# PCB_PSU_DCDC_001_A1.net
KiCad netlist of a schematic drawn in Altium Designer
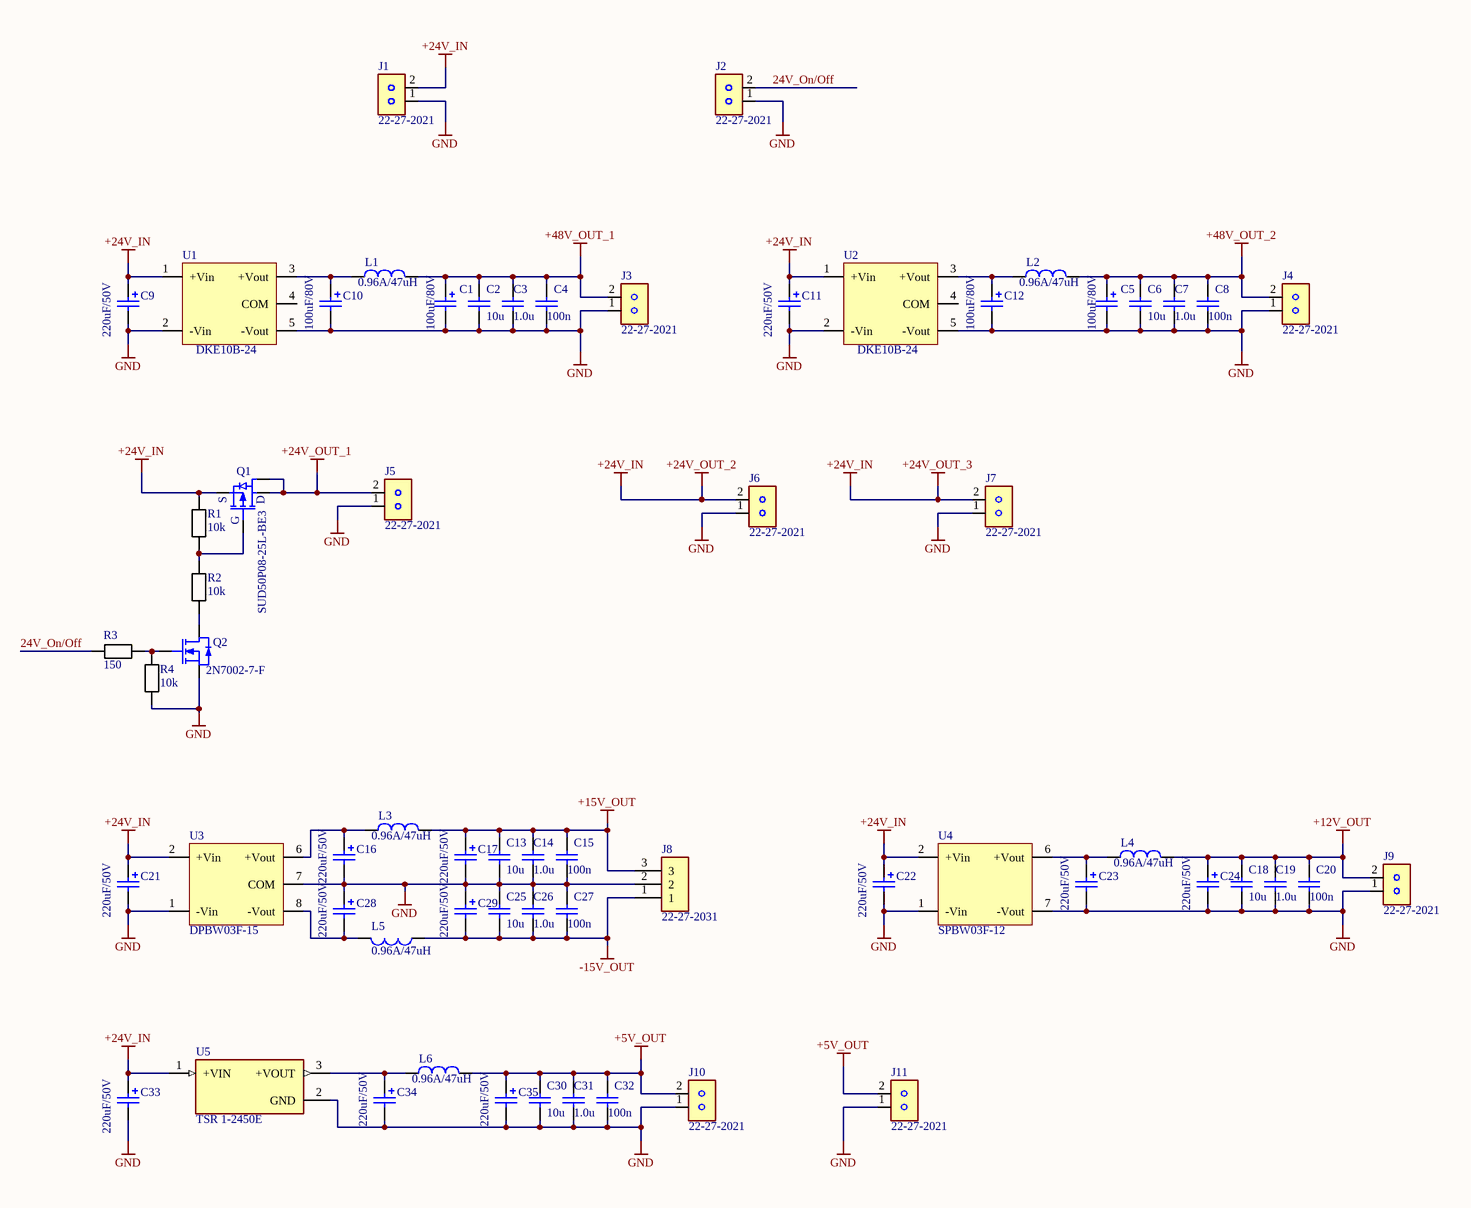
[diagram p0: PCB.PSU.DCDC.001.A1.SchDoc]

(export (version "E")
  (design (tool "Eeschema 10.0.6"))
  (components
    (comp (ref "C1")
      (value "100uF/80V")
      (footprint "CAP_EEU-FS1K101B")
      (description "CAP ALUM 220UF 20% 50V SMD")
      (fields (field (name "MPN") "EEU-FS1K101B") (field (name "MFR") "KEMET"))
      (libsource (lib "PCB.PSU.DCDC.001.A1") (part "Cap_Electrolytic"))
    )
    (comp (ref "C2")
      (value "10u")
      (footprint "C1206")
      (description "Capacitor 10u 1206 +-10% 25V")
      (fields (field (name "MFR") "Yageo") (field (name "MPN") "CC1206KKX7R8BB106"))
      (libsource (lib "Inverter_2kW") (part "CAP_YAG_CC1206KKX7R8BB106"))
    )
    (comp (ref "C3")
      (value "1.0u")
      (footprint "C0603")
      (description "Capacitor 1.0u 0603 +-10% 50V")
      (fields (field (name "PART NUMBER") "CAP_YAG_CC0603KRX7R9BB105_X7R") (field (name "MFR") "Yageo"))
      (libsource (lib "Cap_Yag_0603_X7R_50_10%$") (part "CAP_YAG_CC0603KRX7R9BB105_X7R"))
    )
    (comp (ref "C4")
      (value "100n")
      (footprint "C0603")
      (description "Capacitor 100n 0603 +-10% 50V")
      (fields
        (field (name "PART NUMBER") "CAP_YAG_CC0603KRX7R9BB104_X7R")
        (field (name "MPN") "CC0603KRX7R9BB104")
      )
      (libsource (lib "Cap_Yag_0603_X7R_50_10%$") (part "CAP_YAG_CC0603KRX7R9BB104_X7R"))
    )
    (comp (ref "C5")
      (value "100uF/80V")
      (footprint "CAP_EEU-FS1K101B")
      (description "CAP ALUM 220UF 20% 50V SMD")
      (fields (field (name "MPN") "EEU-FS1K101B") (field (name "MFR") "KEMET"))
      (libsource (lib "PCB.PSU.DCDC.001.A1") (part "Cap_Electrolytic"))
    )
    (comp (ref "C6")
      (value "10u")
      (footprint "C1206")
      (description "Capacitor 10u 1206 +-10% 25V")
      (fields (field (name "MFR") "Yageo") (field (name "MPN") "CC1206KKX7R8BB106"))
      (libsource (lib "Inverter_2kW") (part "CAP_YAG_CC1206KKX7R8BB106"))
    )
    (comp (ref "C7")
      (value "1.0u")
      (footprint "C0603")
      (description "Capacitor 1.0u 0603 +-10% 50V")
      (fields (field (name "PART NUMBER") "CAP_YAG_CC0603KRX7R9BB105_X7R") (field (name "MFR") "Yageo"))
      (libsource (lib "Cap_Yag_0603_X7R_50_10%$") (part "CAP_YAG_CC0603KRX7R9BB105_X7R"))
    )
    (comp (ref "C8")
      (value "100n")
      (footprint "C0603")
      (description "Capacitor 100n 0603 +-10% 50V")
      (fields
        (field (name "PART NUMBER") "CAP_YAG_CC0603KRX7R9BB104_X7R")
        (field (name "MPN") "CC0603KRX7R9BB104")
      )
      (libsource (lib "Cap_Yag_0603_X7R_50_10%$") (part "CAP_YAG_CC0603KRX7R9BB104_X7R"))
    )
    (comp (ref "C9")
      (value "220uF/50V")
      (footprint "CAP_ESL227M050AH8AA")
      (description "CAP ALUM 220UF 20% 50V SMD")
      (fields (field (name "MPN") "ESL227M050AH8AA") (field (name "MFR") "KEMET"))
      (libsource (lib "PCB.PSU.DCDC.001.A1") (part "Cap_Electrolytic"))
    )
    (comp (ref "C10")
      (value "100uF/80V")
      (footprint "CAP_EEU-FS1K101B")
      (description "CAP ALUM 220UF 20% 50V SMD")
      (fields (field (name "MPN") "EEU-FS1K101B") (field (name "MFR") "KEMET"))
      (libsource (lib "PCB.PSU.DCDC.001.A1") (part "Cap_Electrolytic"))
    )
    (comp (ref "C11")
      (value "220uF/50V")
      (footprint "CAP_ESL227M050AH8AA")
      (description "CAP ALUM 220UF 20% 50V SMD")
      (fields (field (name "MPN") "ESL227M050AH8AA") (field (name "MFR") "KEMET"))
      (libsource (lib "PCB.PSU.DCDC.001.A1") (part "Cap_Electrolytic"))
    )
    (comp (ref "C12")
      (value "100uF/80V")
      (footprint "CAP_EEU-FS1K101B")
      (description "CAP ALUM 220UF 20% 50V SMD")
      (fields (field (name "MPN") "EEU-FS1K101B") (field (name "MFR") "KEMET"))
      (libsource (lib "PCB.PSU.DCDC.001.A1") (part "Cap_Electrolytic"))
    )
    (comp (ref "C13")
      (value "10u")
      (footprint "C1206")
      (description "Capacitor 10u 1206 +-10% 25V")
      (fields (field (name "MFR") "Yageo") (field (name "MPN") "CC1206KKX7R8BB106"))
      (libsource (lib "Inverter_2kW") (part "CAP_YAG_CC1206KKX7R8BB106"))
    )
    (comp (ref "C14")
      (value "1.0u")
      (footprint "C0603")
      (description "Capacitor 1.0u 0603 +-10% 50V")
      (fields (field (name "PART NUMBER") "CAP_YAG_CC0603KRX7R9BB105_X7R") (field (name "MFR") "Yageo"))
      (libsource (lib "Cap_Yag_0603_X7R_50_10%$") (part "CAP_YAG_CC0603KRX7R9BB105_X7R"))
    )
    (comp (ref "C15")
      (value "100n")
      (footprint "C0603")
      (description "Capacitor 100n 0603 +-10% 50V")
      (fields
        (field (name "PART NUMBER") "CAP_YAG_CC0603KRX7R9BB104_X7R")
        (field (name "MPN") "CC0603KRX7R9BB104")
      )
      (libsource (lib "Cap_Yag_0603_X7R_50_10%$") (part "CAP_YAG_CC0603KRX7R9BB104_X7R"))
    )
    (comp (ref "C16")
      (value "220uF/50V")
      (footprint "CAP_ESL227M050AH8AA")
      (description "CAP ALUM 220UF 20% 50V SMD")
      (fields (field (name "MPN") "ESL227M050AH8AA") (field (name "MFR") "KEMET"))
      (libsource (lib "PCB.PSU.DCDC.001.A1") (part "Cap_Electrolytic"))
    )
    (comp (ref "C17")
      (value "220uF/50V")
      (footprint "CAP_ESL227M050AH8AA")
      (description "CAP ALUM 220UF 20% 50V SMD")
      (fields (field (name "MPN") "ESL227M050AH8AA") (field (name "MFR") "KEMET"))
      (libsource (lib "PCB.PSU.DCDC.001.A1") (part "Cap_Electrolytic"))
    )
    (comp (ref "C18")
      (value "10u")
      (footprint "C1206")
      (description "Capacitor 10u 1206 +-10% 25V")
      (fields (field (name "MFR") "Yageo") (field (name "MPN") "CC1206KKX7R8BB106"))
      (libsource (lib "Inverter_2kW") (part "CAP_YAG_CC1206KKX7R8BB106"))
    )
    (comp (ref "C19")
      (value "1.0u")
      (footprint "C0603")
      (description "Capacitor 1.0u 0603 +-10% 50V")
      (fields (field (name "PART NUMBER") "CAP_YAG_CC0603KRX7R9BB105_X7R") (field (name "MFR") "Yageo"))
      (libsource (lib "Cap_Yag_0603_X7R_50_10%$") (part "CAP_YAG_CC0603KRX7R9BB105_X7R"))
    )
    (comp (ref "C20")
      (value "100n")
      (footprint "C0603")
      (description "Capacitor 100n 0603 +-10% 50V")
      (fields
        (field (name "PART NUMBER") "CAP_YAG_CC0603KRX7R9BB104_X7R")
        (field (name "MPN") "CC0603KRX7R9BB104")
      )
      (libsource (lib "Cap_Yag_0603_X7R_50_10%$") (part "CAP_YAG_CC0603KRX7R9BB104_X7R"))
    )
    (comp (ref "C21")
      (value "220uF/50V")
      (footprint "CAP_ESL227M050AH8AA")
      (description "CAP ALUM 220UF 20% 50V SMD")
      (fields (field (name "MPN") "ESL227M050AH8AA") (field (name "MFR") "KEMET"))
      (libsource (lib "PCB.PSU.DCDC.001.A1") (part "Cap_Electrolytic"))
    )
    (comp (ref "C22")
      (value "220uF/50V")
      (footprint "CAP_ESL227M050AH8AA")
      (description "CAP ALUM 220UF 20% 50V SMD")
      (fields (field (name "MPN") "ESL227M050AH8AA") (field (name "MFR") "KEMET"))
      (libsource (lib "PCB.PSU.DCDC.001.A1") (part "Cap_Electrolytic"))
    )
    (comp (ref "C23")
      (value "220uF/50V")
      (footprint "CAP_ESL227M050AH8AA")
      (description "CAP ALUM 220UF 20% 50V SMD")
      (fields (field (name "MPN") "ESL227M050AH8AA") (field (name "MFR") "KEMET"))
      (libsource (lib "PCB.PSU.DCDC.001.A1") (part "Cap_Electrolytic"))
    )
    (comp (ref "C24")
      (value "220uF/50V")
      (footprint "CAP_ESL227M050AH8AA")
      (description "CAP ALUM 220UF 20% 50V SMD")
      (fields (field (name "MPN") "ESL227M050AH8AA") (field (name "MFR") "KEMET"))
      (libsource (lib "PCB.PSU.DCDC.001.A1") (part "Cap_Electrolytic"))
    )
    (comp (ref "C25")
      (value "10u")
      (footprint "C1206")
      (description "Capacitor 10u 1206 +-10% 25V")
      (fields (field (name "MFR") "Yageo") (field (name "MPN") "CC1206KKX7R8BB106"))
      (libsource (lib "Inverter_2kW") (part "CAP_YAG_CC1206KKX7R8BB106"))
    )
    (comp (ref "C26")
      (value "1.0u")
      (footprint "C0603")
      (description "Capacitor 1.0u 0603 +-10% 50V")
      (fields (field (name "PART NUMBER") "CAP_YAG_CC0603KRX7R9BB105_X7R") (field (name "MFR") "Yageo"))
      (libsource (lib "Cap_Yag_0603_X7R_50_10%$") (part "CAP_YAG_CC0603KRX7R9BB105_X7R"))
    )
    (comp (ref "C27")
      (value "100n")
      (footprint "C0603")
      (description "Capacitor 100n 0603 +-10% 50V")
      (fields
        (field (name "PART NUMBER") "CAP_YAG_CC0603KRX7R9BB104_X7R")
        (field (name "MPN") "CC0603KRX7R9BB104")
      )
      (libsource (lib "Cap_Yag_0603_X7R_50_10%$") (part "CAP_YAG_CC0603KRX7R9BB104_X7R"))
    )
    (comp (ref "C28")
      (value "220uF/50V")
      (footprint "CAP_ESL227M050AH8AA")
      (description "CAP ALUM 220UF 20% 50V SMD")
      (fields (field (name "MPN") "ESL227M050AH8AA") (field (name "MFR") "KEMET"))
      (libsource (lib "PCB.PSU.DCDC.001.A1") (part "Cap_Electrolytic"))
    )
    (comp (ref "C29")
      (value "220uF/50V")
      (footprint "CAP_ESL227M050AH8AA")
      (description "CAP ALUM 220UF 20% 50V SMD")
      (fields (field (name "MPN") "ESL227M050AH8AA") (field (name "MFR") "KEMET"))
      (libsource (lib "PCB.PSU.DCDC.001.A1") (part "Cap_Electrolytic"))
    )
    (comp (ref "C30")
      (value "10u")
      (footprint "C1206")
      (description "Capacitor 10u 1206 +-10% 25V")
      (fields (field (name "MFR") "Yageo") (field (name "MPN") "CC1206KKX7R8BB106"))
      (libsource (lib "Inverter_2kW") (part "CAP_YAG_CC1206KKX7R8BB106"))
    )
    (comp (ref "C31")
      (value "1.0u")
      (footprint "C0603")
      (description "Capacitor 1.0u 0603 +-10% 50V")
      (fields (field (name "PART NUMBER") "CAP_YAG_CC0603KRX7R9BB105_X7R") (field (name "MFR") "Yageo"))
      (libsource (lib "Cap_Yag_0603_X7R_50_10%$") (part "CAP_YAG_CC0603KRX7R9BB105_X7R"))
    )
    (comp (ref "C32")
      (value "100n")
      (footprint "C0603")
      (description "Capacitor 100n 0603 +-10% 50V")
      (fields
        (field (name "PART NUMBER") "CAP_YAG_CC0603KRX7R9BB104_X7R")
        (field (name "MPN") "CC0603KRX7R9BB104")
      )
      (libsource (lib "Cap_Yag_0603_X7R_50_10%$") (part "CAP_YAG_CC0603KRX7R9BB104_X7R"))
    )
    (comp (ref "C33")
      (value "220uF/50V")
      (footprint "CAP_ESL227M050AH8AA")
      (description "CAP ALUM 220UF 20% 50V SMD")
      (fields (field (name "MPN") "ESL227M050AH8AA") (field (name "MFR") "KEMET"))
      (libsource (lib "PCB.PSU.DCDC.001.A1") (part "Cap_Electrolytic"))
    )
    (comp (ref "C34")
      (value "220uF/50V")
      (footprint "CAP_ESL227M050AH8AA")
      (description "CAP ALUM 220UF 20% 50V SMD")
      (fields (field (name "MPN") "ESL227M050AH8AA") (field (name "MFR") "KEMET"))
      (libsource (lib "PCB.PSU.DCDC.001.A1") (part "Cap_Electrolytic"))
    )
    (comp (ref "C35")
      (value "220uF/50V")
      (footprint "CAP_ESL227M050AH8AA")
      (description "CAP ALUM 220UF 20% 50V SMD")
      (fields (field (name "MPN") "ESL227M050AH8AA") (field (name "MFR") "KEMET"))
      (libsource (lib "PCB.PSU.DCDC.001.A1") (part "Cap_Electrolytic"))
    )
    (comp (ref "J1")
      (value "22-27-2021")
      (footprint "MOLEX_22-27-2021")
      (description "Connector Wire to Board Header 2 Position 2.54mm Solder Straight Thru-Hole Ba")
      (fields (field (name "MFR") "Molex"))
      (libsource (lib "") (part "22-27-2021_1"))
    )
    (comp (ref "J2")
      (value "22-27-2021")
      (footprint "MOLEX_22-27-2021")
      (description "Connector Wire to Board Header 2 Position 2.54mm Solder Straight Thru-Hole Ba")
      (fields (field (name "MFR") "Molex"))
      (libsource (lib "") (part "22-27-2021_1"))
    )
    (comp (ref "J3")
      (value "22-27-2021")
      (footprint "MOLEX_22-27-2021")
      (description "Connector Wire to Board Header 2 Position 2.54mm Solder Straight Thru-Hole Ba")
      (fields (field (name "MFR") "Molex"))
      (libsource (lib "PCB.PSU.DCDC.001.A1") (part "22-27-2021"))
    )
    (comp (ref "J4")
      (value "22-27-2021")
      (footprint "MOLEX_22-27-2021")
      (description "Connector Wire to Board Header 2 Position 2.54mm Solder Straight Thru-Hole Ba")
      (fields (field (name "MFR") "Molex"))
      (libsource (lib "PCB.PSU.DCDC.001.A1") (part "22-27-2021"))
    )
    (comp (ref "J5")
      (value "22-27-2021")
      (footprint "MOLEX_22-27-2021")
      (description "Connector Wire to Board Header 2 Position 2.54mm Solder Straight Thru-Hole Ba")
      (fields (field (name "MFR") "Molex"))
      (libsource (lib "PCB.PSU.DCDC.001.A1") (part "22-27-2021"))
    )
    (comp (ref "J6")
      (value "22-27-2021")
      (footprint "MOLEX_22-27-2021")
      (description "Connector Wire to Board Header 2 Position 2.54mm Solder Straight Thru-Hole Ba")
      (fields (field (name "MFR") "Molex"))
      (libsource (lib "PCB.PSU.DCDC.001.A1") (part "22-27-2021"))
    )
    (comp (ref "J7")
      (value "22-27-2021")
      (footprint "MOLEX_22-27-2021")
      (description "Connector Wire to Board Header 2 Position 2.54mm Solder Straight Thru-Hole Ba")
      (fields (field (name "MFR") "Molex"))
      (libsource (lib "PCB.PSU.DCDC.001.A1") (part "22-27-2021"))
    )
    (comp (ref "J8")
      (value "22-27-2031")
      (footprint "MOLEX_22-27-2031")
      (description "Connector Header Through Hole 3 position 0.100 _2.54mm_")
      (fields (field (name "MFR") "Molex"))
      (libsource (lib "PCB.PSU.DCDC.001.A1") (part "22-27-2031"))
    )
    (comp (ref "J9")
      (value "22-27-2021")
      (footprint "MOLEX_22-27-2021")
      (description "Connector Wire to Board Header 2 Position 2.54mm Solder Straight Thru-Hole Ba")
      (fields (field (name "MFR") "Molex"))
      (libsource (lib "PCB.PSU.DCDC.001.A1") (part "22-27-2021"))
    )
    (comp (ref "J10")
      (value "22-27-2021")
      (footprint "MOLEX_22-27-2021")
      (description "Connector Wire to Board Header 2 Position 2.54mm Solder Straight Thru-Hole Ba")
      (fields (field (name "MFR") "Molex"))
      (libsource (lib "PCB.PSU.DCDC.001.A1") (part "22-27-2021"))
    )
    (comp (ref "J11")
      (value "22-27-2021")
      (footprint "MOLEX_22-27-2021")
      (description "Connector Wire to Board Header 2 Position 2.54mm Solder Straight Thru-Hole Ba")
      (fields (field (name "MFR") "Molex"))
      (libsource (lib "PCB.PSU.DCDC.001.A1") (part "22-27-2021"))
    )
    (comp (ref "L1")
      (value "0.96A/47uH")
      (footprint "IND_RLB0912")
      (description "Power Inductors - Leaded 47uH 10% .96A")
      (fields (field (name "MFR") "Bourns") (field (name "MPN") "RLB0912-470KL"))
      (libsource (lib "34-413 - IPM2 Smart BoB 2Ch CC") (part "Inductor"))
    )
    (comp (ref "L2")
      (value "0.96A/47uH")
      (footprint "IND_RLB0912")
      (description "Power Inductors - Leaded 47uH 10% .96A")
      (fields (field (name "MFR") "Bourns") (field (name "MPN") "RLB0912-470KL"))
      (libsource (lib "34-413 - IPM2 Smart BoB 2Ch CC") (part "Inductor"))
    )
    (comp (ref "L3")
      (value "0.96A/47uH")
      (footprint "IND_RLB0912")
      (description "Power Inductors - Leaded 47uH 10% .96A")
      (fields (field (name "MFR") "Bourns") (field (name "MPN") "RLB0912-470KL"))
      (libsource (lib "34-413 - IPM2 Smart BoB 2Ch CC") (part "Inductor"))
    )
    (comp (ref "L4")
      (value "0.96A/47uH")
      (footprint "IND_RLB0912")
      (description "Power Inductors - Leaded 47uH 10% .96A")
      (fields (field (name "MFR") "Bourns") (field (name "MPN") "RLB0912-470KL"))
      (libsource (lib "34-413 - IPM2 Smart BoB 2Ch CC") (part "Inductor"))
    )
    (comp (ref "L5")
      (value "0.96A/47uH")
      (footprint "IND_RLB0912")
      (description "Power Inductors - Leaded 47uH 10% .96A")
      (fields (field (name "MFR") "Bourns") (field (name "MPN") "RLB0912-470KL"))
      (libsource (lib "34-413 - IPM2 Smart BoB 2Ch CC") (part "Inductor"))
    )
    (comp (ref "L6")
      (value "0.96A/47uH")
      (footprint "IND_RLB0912")
      (description "Power Inductors - Leaded 47uH 10% .96A")
      (fields (field (name "MFR") "Bourns") (field (name "MPN") "RLB0912-470KL"))
      (libsource (lib "34-413 - IPM2 Smart BoB 2Ch CC") (part "Inductor"))
    )
    (comp (ref "Q1")
      (value "SUD50P08-25L-BE3")
      (footprint "TO-252-3")
      (description "MOSFET 80V P-CH MOSFET (D-S) 17")
      (fields (field (name "MFR") "Vishay"))
      (libsource (lib "47-750 - DriveHub IPM2 Multi-Channel Rx") (part "SUD50P08-25L-BE3"))
    )
    (comp (ref "Q2")
      (value "2N7002-7-F")
      (footprint "SOT23-3N")
      (description "MOSFET N-CH 60V 200MA SOT23-3")
      (fields (field (name "MFR") "Diodes Incorporated"))
      (libsource (lib "BidirectionalCharger") (part "MOSFET-N"))
    )
    (comp (ref "R1")
      (value "10k")
      (footprint "R0603")
      (description "Resistor 10k 0603 +-1% 0.1")
      (fields (field (name "PART NUMBER") "RES_YAG_RC0603FR-0710KL") (field (name "MFR") "Yageo"))
      (libsource (lib "Res_Yag_0603_1%$") (part "RES_YAG_RC0603FR-0710KL"))
    )
    (comp (ref "R2")
      (value "10k")
      (footprint "R0603")
      (description "Resistor 10k 0603 +-1% 0.1")
      (fields (field (name "PART NUMBER") "RES_YAG_RC0603FR-0710KL") (field (name "MFR") "Yageo"))
      (libsource (lib "Res_Yag_0603_1%$") (part "RES_YAG_RC0603FR-0710KL"))
    )
    (comp (ref "R3")
      (value "150")
      (footprint "R0603")
      (description "Resistor 150 0603 +-1% 0.1")
      (fields (field (name "PART NUMBER") "RES_YAG_RC0603FR-07150RL") (field (name "MFR") "Yageo"))
      (libsource (lib "Res_Yag_0603_1%$") (part "RES_YAG_RC0603FR-07150RL"))
    )
    (comp (ref "R4")
      (value "10k")
      (footprint "R0603")
      (description "Resistor 10k 0603 +-1% 0.1")
      (fields (field (name "PART NUMBER") "RES_YAG_RC0603FR-0710KL") (field (name "MFR") "Yageo"))
      (libsource (lib "Res_Yag_0603_1%$") (part "RES_YAG_RC0603FR-0710KL"))
    )
    (comp (ref "U1")
      (value "DKE10B-24")
      (footprint "DKE10B-24")
      (description "Isolated DC/DC Converters - Through Hole 18-36Vin +/-24Vout 21-210mA, 10W")
      (fields (field (name "MFR") "MEAN WELL"))
      (libsource (lib "PCB.PSU.DCDC.001.A1") (part "DKE10B-24"))
    )
    (comp (ref "U2")
      (value "DKE10B-24")
      (footprint "DKE10B-24")
      (description "Isolated DC/DC Converters - Through Hole 18-36Vin +/-24Vout 21-210mA, 10W")
      (fields (field (name "MFR") "MEAN WELL"))
      (libsource (lib "PCB.PSU.DCDC.001.A1") (part "DKE10B-24"))
    )
    (comp (ref "U3")
      (value "DPBW03F-15")
      (footprint "DPBW03F-15")
      (description "Isolated DC/DC Converters - Through Hole 9-36Vin +/-15Vout +/-100mA SIP Reg Iso")
      (fields (field (name "MFR") "MEAN WELL"))
      (libsource (lib "PCB.PSU.DCDC.001.A1") (part "DPBW03F-15"))
    )
    (comp (ref "U4")
      (value "SPBW03F-12")
      (footprint "SPBW03F-12")
      (description "Isolated DC/DC Converters - Through Hole 9-36Vin 12Vout 250mA SIP8 Reg Iso")
      (fields (field (name "MFR") "MEAN WELL"))
      (libsource (lib "PCB.PSU.DCDC.001.A1") (part "SPBW03F-12"))
    )
    (comp (ref "U5")
      (value "TSR 1-2450E")
      (footprint "CONV_TSR_1-2450E")
      (fields (field (name "MFR") "Traco Power"))
      (libsource (lib "PCB.PSU.DCDC.001.A1") (part "TSR_1-2450E"))
    )
  )
  (nets
    (net (code "1") (name "+5V_OUT") (class "Default")
      (node (ref "C30") (pin "2") (pinfunction "2_2") (pintype "passive"))
      (node (ref "C31") (pin "2") (pinfunction "2_2") (pintype "passive"))
      (node (ref "C32") (pin "2") (pinfunction "2_2") (pintype "passive"))
      (node (ref "C35") (pin "1") (pinfunction "1_1") (pintype "passive"))
      (node (ref "J10") (pin "2") (pinfunction "2_2") (pintype "passive"))
      (node (ref "J11") (pin "2") (pinfunction "2_2") (pintype "passive"))
      (node (ref "L6") (pin "2") (pinfunction "2_2") (pintype "passive"))
    )
    (net (code "2") (name "+12V_OUT") (class "Default")
      (node (ref "C18") (pin "2") (pinfunction "2_2") (pintype "passive"))
      (node (ref "C19") (pin "2") (pinfunction "2_2") (pintype "passive"))
      (node (ref "C20") (pin "2") (pinfunction "2_2") (pintype "passive"))
      (node (ref "C24") (pin "1") (pinfunction "1_1") (pintype "passive"))
      (node (ref "J9") (pin "2") (pinfunction "2_2") (pintype "passive"))
      (node (ref "L4") (pin "2") (pinfunction "2_2") (pintype "passive"))
    )
    (net (code "3") (name "+15V_OUT") (class "Default")
      (node (ref "C13") (pin "2") (pinfunction "2_2") (pintype "passive"))
      (node (ref "C14") (pin "2") (pinfunction "2_2") (pintype "passive"))
      (node (ref "C15") (pin "2") (pinfunction "2_2") (pintype "passive"))
      (node (ref "C17") (pin "1") (pinfunction "1_1") (pintype "passive"))
      (node (ref "J8") (pin "3") (pinfunction "3_3") (pintype "passive"))
      (node (ref "L3") (pin "2") (pinfunction "2_2") (pintype "passive"))
    )
    (net (code "4") (name "+24V_IN") (class "Default")
      (node (ref "C11") (pin "1") (pinfunction "1_1") (pintype "passive"))
      (node (ref "C21") (pin "1") (pinfunction "1_1") (pintype "passive"))
      (node (ref "C22") (pin "1") (pinfunction "1_1") (pintype "passive"))
      (node (ref "C33") (pin "1") (pinfunction "1_1") (pintype "passive"))
      (node (ref "C9") (pin "1") (pinfunction "1_1") (pintype "passive"))
      (node (ref "J1") (pin "2") (pinfunction "2_2") (pintype "passive"))
      (node (ref "J6") (pin "2") (pinfunction "2_2") (pintype "passive"))
      (node (ref "J7") (pin "2") (pinfunction "2_2") (pintype "passive"))
      (node (ref "Q1") (pin "3") (pinfunction "S_3") (pintype "passive"))
      (node (ref "R1") (pin "2") (pinfunction "2_2") (pintype "passive"))
      (node (ref "U1") (pin "1") (pinfunction "+Vin_1") (pintype "passive"))
      (node (ref "U2") (pin "1") (pinfunction "+Vin_1") (pintype "passive"))
      (node (ref "U3") (pin "2") (pinfunction "+Vin_2") (pintype "passive"))
      (node (ref "U4") (pin "2") (pinfunction "+Vin_2") (pintype "passive"))
      (node (ref "U5") (pin "1") (pinfunction "+VIN_1") (pintype "input"))
    )
    (net (code "5") (name "+24V_OUT_1") (class "Default")
      (node (ref "J5") (pin "2") (pinfunction "2_2") (pintype "passive"))
      (node (ref "Q1") (pin "2") (pinfunction "D_2") (pintype "passive"))
    )
    (net (code "6") (name "+48V_OUT_1") (class "Default")
      (node (ref "C1") (pin "1") (pinfunction "1_1") (pintype "passive"))
      (node (ref "C2") (pin "2") (pinfunction "2_2") (pintype "passive"))
      (node (ref "C3") (pin "2") (pinfunction "2_2") (pintype "passive"))
      (node (ref "C4") (pin "2") (pinfunction "2_2") (pintype "passive"))
      (node (ref "J3") (pin "2") (pinfunction "2_2") (pintype "passive"))
      (node (ref "L1") (pin "2") (pinfunction "2_2") (pintype "passive"))
    )
    (net (code "7") (name "+48V_OUT_2") (class "Default")
      (node (ref "C5") (pin "1") (pinfunction "1_1") (pintype "passive"))
      (node (ref "C6") (pin "2") (pinfunction "2_2") (pintype "passive"))
      (node (ref "C7") (pin "2") (pinfunction "2_2") (pintype "passive"))
      (node (ref "C8") (pin "2") (pinfunction "2_2") (pintype "passive"))
      (node (ref "J4") (pin "2") (pinfunction "2_2") (pintype "passive"))
      (node (ref "L2") (pin "2") (pinfunction "2_2") (pintype "passive"))
    )
    (net (code "8") (name "-15V_OUT") (class "Default")
      (node (ref "C25") (pin "1") (pinfunction "1_1") (pintype "passive"))
      (node (ref "C26") (pin "1") (pinfunction "1_1") (pintype "passive"))
      (node (ref "C27") (pin "1") (pinfunction "1_1") (pintype "passive"))
      (node (ref "C29") (pin "2") (pinfunction "2_2") (pintype "passive"))
      (node (ref "J8") (pin "1") (pinfunction "1_1") (pintype "passive"))
      (node (ref "L5") (pin "1") (pinfunction "1_1") (pintype "passive"))
    )
    (net (code "9") (name "/24V_On{slash}Off") (class "Default")
      (node (ref "J2") (pin "2") (pinfunction "2_2") (pintype "passive"))
      (node (ref "R3") (pin "1") (pinfunction "1_1") (pintype "passive"))
    )
    (net (code "10") (name "GND") (class "Default")
      (node (ref "C1") (pin "2") (pinfunction "2_2") (pintype "passive"))
      (node (ref "C10") (pin "2") (pinfunction "2_2") (pintype "passive"))
      (node (ref "C11") (pin "2") (pinfunction "2_2") (pintype "passive"))
      (node (ref "C12") (pin "2") (pinfunction "2_2") (pintype "passive"))
      (node (ref "C13") (pin "1") (pinfunction "1_1") (pintype "passive"))
      (node (ref "C14") (pin "1") (pinfunction "1_1") (pintype "passive"))
      (node (ref "C15") (pin "1") (pinfunction "1_1") (pintype "passive"))
      (node (ref "C16") (pin "2") (pinfunction "2_2") (pintype "passive"))
      (node (ref "C17") (pin "2") (pinfunction "2_2") (pintype "passive"))
      (node (ref "C18") (pin "1") (pinfunction "1_1") (pintype "passive"))
      (node (ref "C19") (pin "1") (pinfunction "1_1") (pintype "passive"))
      (node (ref "C2") (pin "1") (pinfunction "1_1") (pintype "passive"))
      (node (ref "C20") (pin "1") (pinfunction "1_1") (pintype "passive"))
      (node (ref "C21") (pin "2") (pinfunction "2_2") (pintype "passive"))
      (node (ref "C22") (pin "2") (pinfunction "2_2") (pintype "passive"))
      (node (ref "C23") (pin "2") (pinfunction "2_2") (pintype "passive"))
      (node (ref "C24") (pin "2") (pinfunction "2_2") (pintype "passive"))
      (node (ref "C25") (pin "2") (pinfunction "2_2") (pintype "passive"))
      (node (ref "C26") (pin "2") (pinfunction "2_2") (pintype "passive"))
      (node (ref "C27") (pin "2") (pinfunction "2_2") (pintype "passive"))
      (node (ref "C28") (pin "1") (pinfunction "1_1") (pintype "passive"))
      (node (ref "C29") (pin "1") (pinfunction "1_1") (pintype "passive"))
      (node (ref "C3") (pin "1") (pinfunction "1_1") (pintype "passive"))
      (node (ref "C30") (pin "1") (pinfunction "1_1") (pintype "passive"))
      (node (ref "C31") (pin "1") (pinfunction "1_1") (pintype "passive"))
      (node (ref "C32") (pin "1") (pinfunction "1_1") (pintype "passive"))
      (node (ref "C33") (pin "2") (pinfunction "2_2") (pintype "passive"))
      (node (ref "C34") (pin "2") (pinfunction "2_2") (pintype "passive"))
      (node (ref "C35") (pin "2") (pinfunction "2_2") (pintype "passive"))
      (node (ref "C4") (pin "1") (pinfunction "1_1") (pintype "passive"))
      (node (ref "C5") (pin "2") (pinfunction "2_2") (pintype "passive"))
      (node (ref "C6") (pin "1") (pinfunction "1_1") (pintype "passive"))
      (node (ref "C7") (pin "1") (pinfunction "1_1") (pintype "passive"))
      (node (ref "C8") (pin "1") (pinfunction "1_1") (pintype "passive"))
      (node (ref "C9") (pin "2") (pinfunction "2_2") (pintype "passive"))
      (node (ref "J1") (pin "1") (pinfunction "1_1") (pintype "passive"))
      (node (ref "J10") (pin "1") (pinfunction "1_1") (pintype "passive"))
      (node (ref "J11") (pin "1") (pinfunction "1_1") (pintype "passive"))
      (node (ref "J2") (pin "1") (pinfunction "1_1") (pintype "passive"))
      (node (ref "J3") (pin "1") (pinfunction "1_1") (pintype "passive"))
      (node (ref "J4") (pin "1") (pinfunction "1_1") (pintype "passive"))
      (node (ref "J5") (pin "1") (pinfunction "1_1") (pintype "passive"))
      (node (ref "J6") (pin "1") (pinfunction "1_1") (pintype "passive"))
      (node (ref "J7") (pin "1") (pinfunction "1_1") (pintype "passive"))
      (node (ref "J8") (pin "2") (pinfunction "2_2") (pintype "passive"))
      (node (ref "J9") (pin "1") (pinfunction "1_1") (pintype "passive"))
      (node (ref "Q2") (pin "2") (pinfunction "S_2") (pintype "passive"))
      (node (ref "R4") (pin "1") (pinfunction "1_1") (pintype "passive"))
      (node (ref "U1") (pin "2") (pinfunction "-Vin_2") (pintype "passive"))
      (node (ref "U1") (pin "5") (pinfunction "-Vout_5") (pintype "passive"))
      (node (ref "U2") (pin "2") (pinfunction "-Vin_2") (pintype "passive"))
      (node (ref "U2") (pin "5") (pinfunction "-Vout_5") (pintype "passive"))
      (node (ref "U3") (pin "1") (pinfunction "-Vin_1") (pintype "passive"))
      (node (ref "U3") (pin "7") (pinfunction "COM_7") (pintype "passive"))
      (node (ref "U4") (pin "1") (pinfunction "-Vin_1") (pintype "passive"))
      (node (ref "U4") (pin "7") (pinfunction "-Vout_7") (pintype "passive"))
      (node (ref "U5") (pin "2") (pinfunction "GND_2") (pintype "power_in"))
    )
    (net (code "11") (name "Net-(Q1-G)") (class "Default")
      (node (ref "Q1") (pin "1") (pinfunction "G_1") (pintype "passive"))
      (node (ref "R1") (pin "1") (pinfunction "1_1") (pintype "passive"))
      (node (ref "R2") (pin "2") (pinfunction "2_2") (pintype "passive"))
    )
    (net (code "12") (name "Net-(Q2-D)") (class "Default")
      (node (ref "Q2") (pin "3") (pinfunction "D_3") (pintype "passive"))
      (node (ref "R2") (pin "1") (pinfunction "1_1") (pintype "passive"))
    )
    (net (code "13") (name "Net-(Q2-G)") (class "Default")
      (node (ref "Q2") (pin "1") (pinfunction "G_1") (pintype "passive"))
      (node (ref "R3") (pin "2") (pinfunction "2_2") (pintype "passive"))
      (node (ref "R4") (pin "2") (pinfunction "2_2") (pintype "passive"))
    )
    (net (code "14") (name "Net-(U1-+Vout)") (class "Default")
      (node (ref "C10") (pin "1") (pinfunction "1_1") (pintype "passive"))
      (node (ref "L1") (pin "1") (pinfunction "1_1") (pintype "passive"))
      (node (ref "U1") (pin "3") (pinfunction "+Vout_3") (pintype "passive"))
    )
    (net (code "15") (name "Net-(U2-+Vout)") (class "Default")
      (node (ref "C12") (pin "1") (pinfunction "1_1") (pintype "passive"))
      (node (ref "L2") (pin "1") (pinfunction "1_1") (pintype "passive"))
      (node (ref "U2") (pin "3") (pinfunction "+Vout_3") (pintype "passive"))
    )
    (net (code "16") (name "Net-(U3-+Vout)") (class "Default")
      (node (ref "C16") (pin "1") (pinfunction "1_1") (pintype "passive"))
      (node (ref "L3") (pin "1") (pinfunction "1_1") (pintype "passive"))
      (node (ref "U3") (pin "6") (pinfunction "+Vout_6") (pintype "passive"))
    )
    (net (code "17") (name "Net-(U3--Vout)") (class "Default")
      (node (ref "C28") (pin "2") (pinfunction "2_2") (pintype "passive"))
      (node (ref "L5") (pin "2") (pinfunction "2_2") (pintype "passive"))
      (node (ref "U3") (pin "8") (pinfunction "-Vout_8") (pintype "passive"))
    )
    (net (code "18") (name "Net-(U4-+Vout)") (class "Default")
      (node (ref "C23") (pin "1") (pinfunction "1_1") (pintype "passive"))
      (node (ref "L4") (pin "1") (pinfunction "1_1") (pintype "passive"))
      (node (ref "U4") (pin "6") (pinfunction "+Vout_6") (pintype "passive"))
    )
    (net (code "19") (name "Net-(U5-+VOUT)") (class "Default")
      (node (ref "C34") (pin "1") (pinfunction "1_1") (pintype "passive"))
      (node (ref "L6") (pin "1") (pinfunction "1_1") (pintype "passive"))
      (node (ref "U5") (pin "3") (pinfunction "+VOUT_3") (pintype "output"))
    )
    (net (code "20") (name "unconnected-(U1-COM-Pad4)") (class "Default")
      (node (ref "U1") (pin "4") (pinfunction "COM_4") (pintype "passive"))
    )
    (net (code "21") (name "unconnected-(U2-COM-Pad4)") (class "Default")
      (node (ref "U2") (pin "4") (pinfunction "COM_4") (pintype "passive"))
    )
  )
)
